# FX_I2C_Proto_Shield_v9.net
KiCad netlist of a schematic drawn in EAGLE
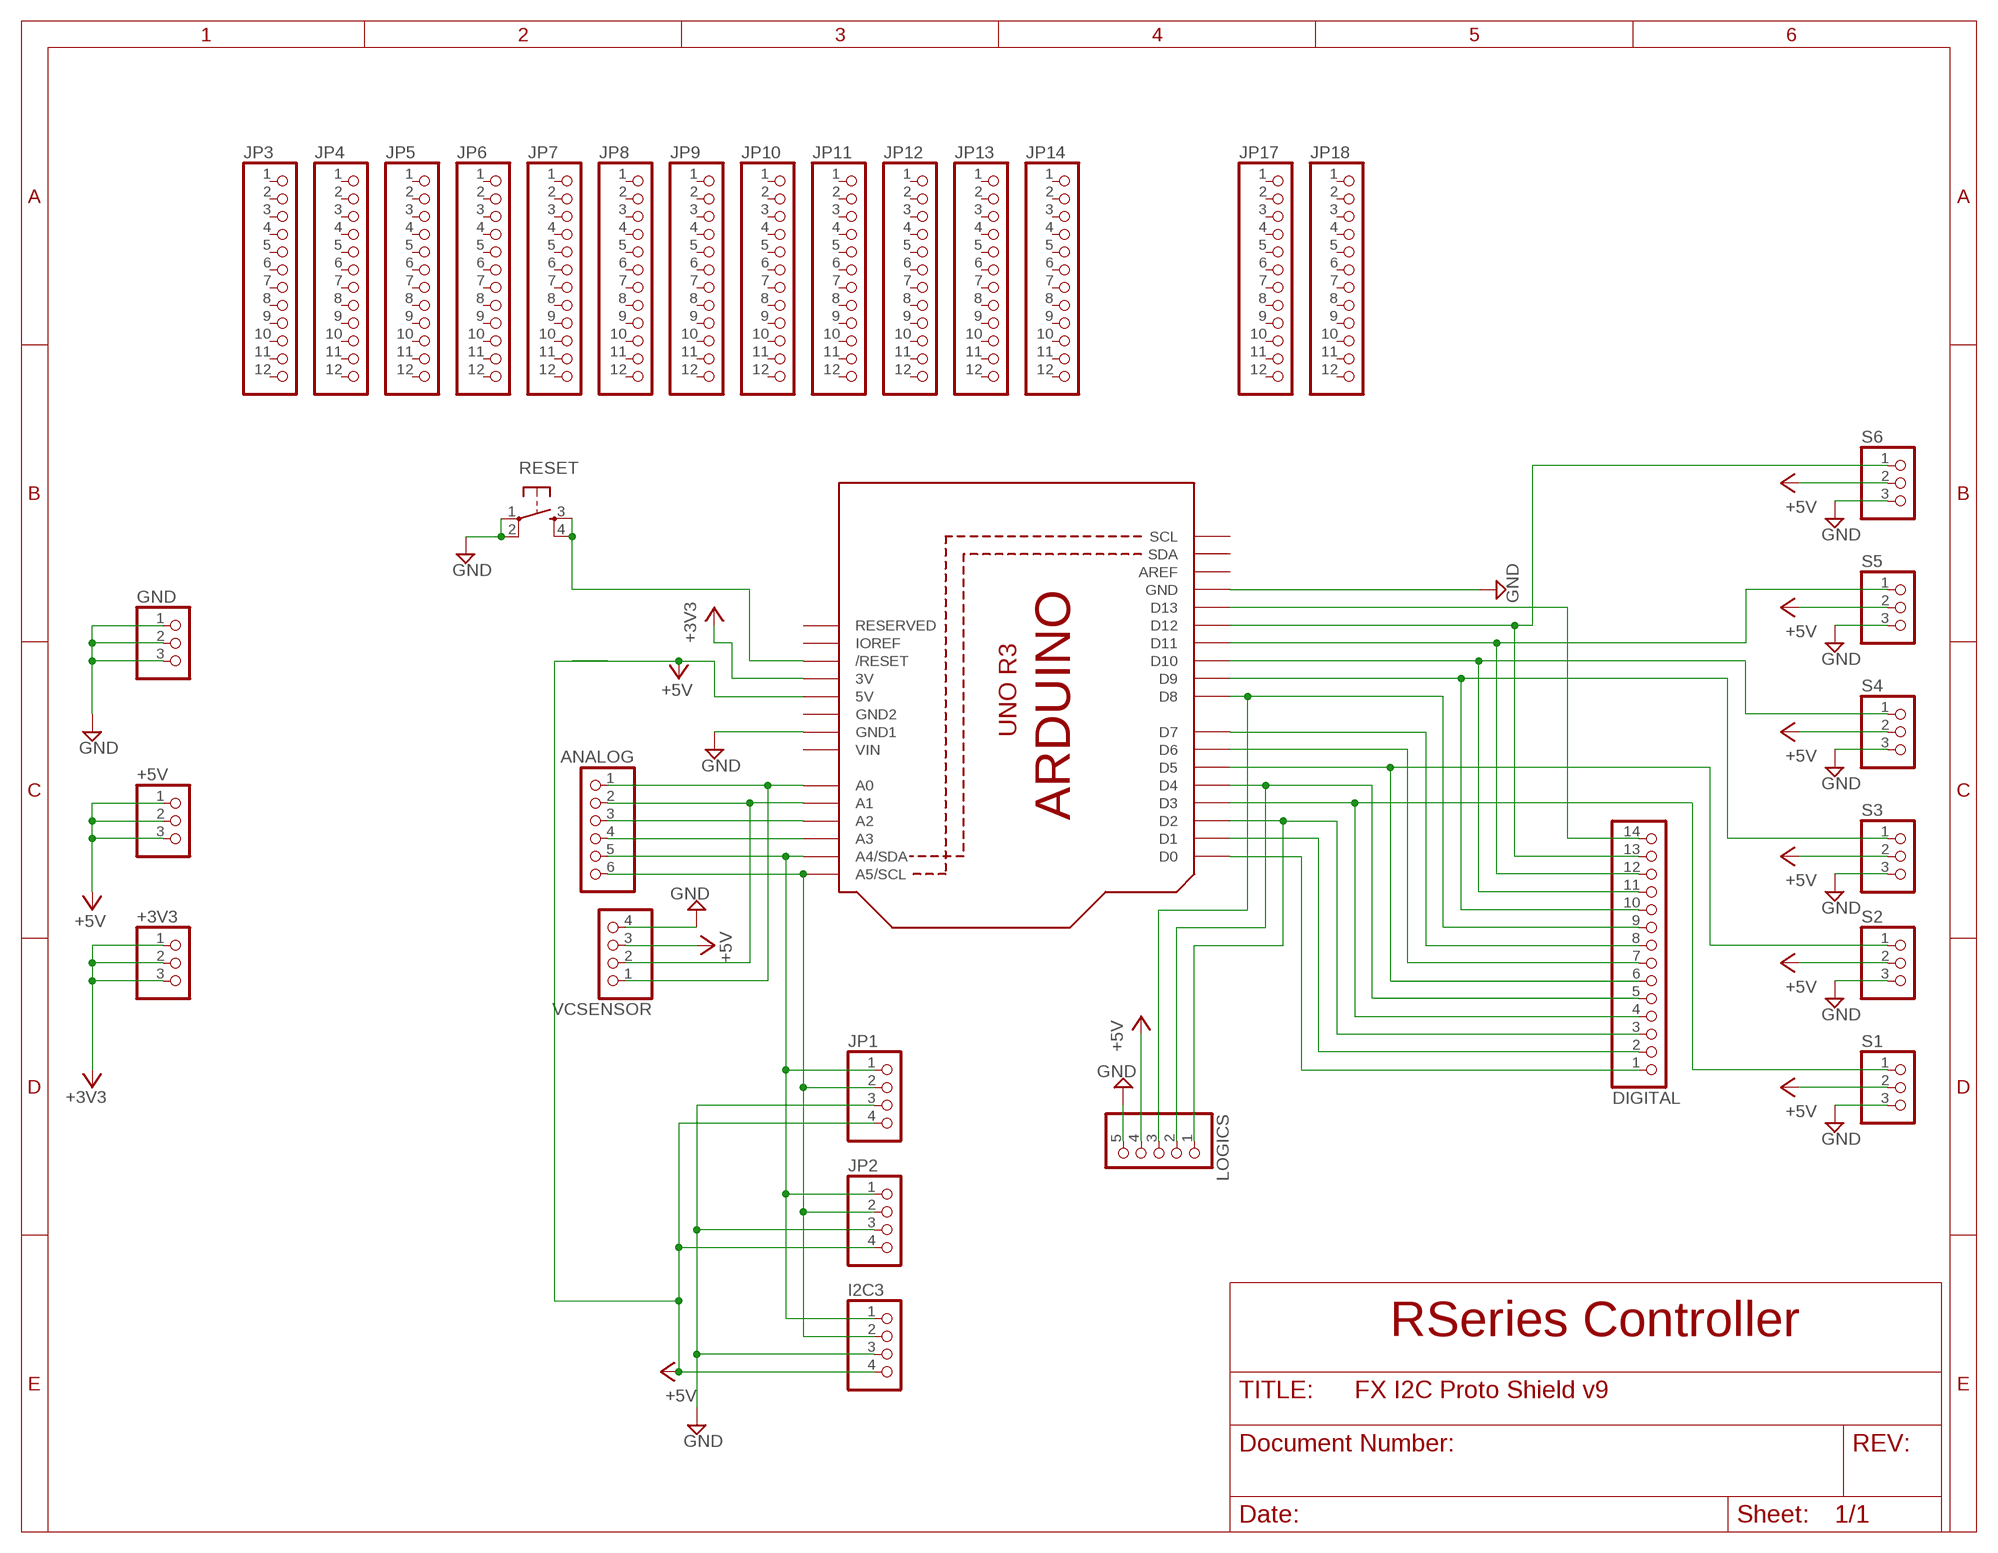
[diagram p0: schematic, sheet 1]

(export (version "E")
  (design (tool "Eeschema 10.0.6"))
  (components
    (comp (ref "+3V3")
      (value "PINHD-1X3CB")
      (footprint "eagle-import:1X03-CLEANBIG")
      (libsource (lib "eagle-import") (part "PINHD-1X3CB"))
    )
    (comp (ref "+5V")
      (value "PINHD-1X3CB")
      (footprint "eagle-import:1X03-CLEANBIG")
      (libsource (lib "eagle-import") (part "PINHD-1X3CB"))
    )
    (comp (ref "ANALOG")
      (value "PINHD-1X6B")
      (footprint "eagle-import:1X06-BIG")
      (libsource (lib "eagle-import") (part "PINHD-1X6B"))
    )
    (comp (ref "DIGITAL")
      (value "PINHD-1X14-CB")
      (footprint "eagle-import:1X14-CB")
      (libsource (lib "eagle-import") (part "PINHD-1X14-CB"))
    )
    (comp (ref "GND")
      (value "PINHD-1X3CB")
      (footprint "eagle-import:1X03-CLEANBIG")
      (libsource (lib "eagle-import") (part "PINHD-1X3CB"))
    )
    (comp (ref "I2C3")
      (value "PINHD-1X4")
      (footprint "eagle-import:1X04")
      (libsource (lib "eagle-import") (part "PINHD-1X4"))
    )
    (comp (ref "JP1")
      (value "PINHD-1X4")
      (footprint "eagle-import:1X04")
      (libsource (lib "eagle-import") (part "PINHD-1X4"))
    )
    (comp (ref "JP2")
      (value "PINHD-1X4")
      (footprint "eagle-import:1X04")
      (libsource (lib "eagle-import") (part "PINHD-1X4"))
    )
    (comp (ref "JP3")
      (value "PINHD-1X12-CB")
      (footprint "eagle-import:1X12-CB")
      (libsource (lib "eagle-import") (part "PINHD-1X12-CB"))
    )
    (comp (ref "JP4")
      (value "PINHD-1X12-CB")
      (footprint "eagle-import:1X12-CB")
      (libsource (lib "eagle-import") (part "PINHD-1X12-CB"))
    )
    (comp (ref "JP5")
      (value "PINHD-1X12-CB")
      (footprint "eagle-import:1X12-CB")
      (libsource (lib "eagle-import") (part "PINHD-1X12-CB"))
    )
    (comp (ref "JP6")
      (value "PINHD-1X12-CB")
      (footprint "eagle-import:1X12-CB")
      (libsource (lib "eagle-import") (part "PINHD-1X12-CB"))
    )
    (comp (ref "JP7")
      (value "PINHD-1X12-CB")
      (footprint "eagle-import:1X12-CB")
      (libsource (lib "eagle-import") (part "PINHD-1X12-CB"))
    )
    (comp (ref "JP8")
      (value "PINHD-1X12-CB")
      (footprint "eagle-import:1X12-CB")
      (libsource (lib "eagle-import") (part "PINHD-1X12-CB"))
    )
    (comp (ref "JP9")
      (value "PINHD-1X12-CB")
      (footprint "eagle-import:1X12-CB")
      (libsource (lib "eagle-import") (part "PINHD-1X12-CB"))
    )
    (comp (ref "JP10")
      (value "PINHD-1X12-CB")
      (footprint "eagle-import:1X12-CB")
      (libsource (lib "eagle-import") (part "PINHD-1X12-CB"))
    )
    (comp (ref "JP11")
      (value "PINHD-1X12-CB")
      (footprint "eagle-import:1X12-CB")
      (libsource (lib "eagle-import") (part "PINHD-1X12-CB"))
    )
    (comp (ref "JP12")
      (value "PINHD-1X12-CB")
      (footprint "eagle-import:1X12-CB")
      (libsource (lib "eagle-import") (part "PINHD-1X12-CB"))
    )
    (comp (ref "JP13")
      (value "PINHD-1X12-CB")
      (footprint "eagle-import:1X12-CB")
      (libsource (lib "eagle-import") (part "PINHD-1X12-CB"))
    )
    (comp (ref "JP14")
      (value "PINHD-1X12-CB")
      (footprint "eagle-import:1X12-CB")
      (libsource (lib "eagle-import") (part "PINHD-1X12-CB"))
    )
    (comp (ref "JP17")
      (value "PINHD-1X12-CB")
      (footprint "eagle-import:1X12-CB")
      (libsource (lib "eagle-import") (part "PINHD-1X12-CB"))
    )
    (comp (ref "JP18")
      (value "PINHD-1X12-CB")
      (footprint "eagle-import:1X12-CB")
      (libsource (lib "eagle-import") (part "PINHD-1X12-CB"))
    )
    (comp (ref "LOGICS")
      (value "PINHD-1X5")
      (footprint "eagle-import:1X05")
      (libsource (lib "eagle-import") (part "PINHD-1X5"))
    )
    (comp (ref "RESET")
      (value "TAC_SWITCHPTH")
      (footprint "eagle-import:TACTILE-PTH")
      (libsource (lib "eagle-import") (part "TAC_SWITCHPTH"))
    )
    (comp (ref "S1")
      (value "PINHD-1X3")
      (footprint "eagle-import:1X03")
      (libsource (lib "eagle-import") (part "PINHD-1X3"))
    )
    (comp (ref "S2")
      (value "PINHD-1X3")
      (footprint "eagle-import:1X03")
      (libsource (lib "eagle-import") (part "PINHD-1X3"))
    )
    (comp (ref "S3")
      (value "PINHD-1X3")
      (footprint "eagle-import:1X03")
      (libsource (lib "eagle-import") (part "PINHD-1X3"))
    )
    (comp (ref "S4")
      (value "PINHD-1X3")
      (footprint "eagle-import:1X03")
      (libsource (lib "eagle-import") (part "PINHD-1X3"))
    )
    (comp (ref "S5")
      (value "PINHD-1X3")
      (footprint "eagle-import:1X03")
      (libsource (lib "eagle-import") (part "PINHD-1X3"))
    )
    (comp (ref "S6")
      (value "PINHD-1X3")
      (footprint "eagle-import:1X03")
      (libsource (lib "eagle-import") (part "PINHD-1X3"))
    )
    (comp (ref "U1")
      (value "ARDUINOR3-DIMENSION")
      (footprint "eagle-import:ARDUINOR3")
      (libsource (lib "eagle-import") (part "ARDUINOR3-DIMENSION"))
    )
    (comp (ref "VCSENSOR")
      (value "PINHD-1X4")
      (footprint "eagle-import:1X04")
      (libsource (lib "eagle-import") (part "PINHD-1X4"))
    )
  )
  (nets
    (net (code "1") (name "+3V3") (class "Default")
      (node (ref "+3V3") (pin "1") (pinfunction "1_1") (pintype "passive"))
      (node (ref "+3V3") (pin "2") (pinfunction "2_2") (pintype "passive"))
      (node (ref "+3V3") (pin "3") (pinfunction "3_3") (pintype "passive"))
      (node (ref "U1") (pin "3V") (pinfunction "3V_3V") (pintype "power_in"))
    )
    (net (code "2") (name "+5V") (class "Default")
      (node (ref "+5V") (pin "1") (pinfunction "1_1") (pintype "passive"))
      (node (ref "+5V") (pin "2") (pinfunction "2_2") (pintype "passive"))
      (node (ref "+5V") (pin "3") (pinfunction "3_3") (pintype "passive"))
      (node (ref "I2C3") (pin "4") (pinfunction "4_4") (pintype "passive"))
      (node (ref "JP1") (pin "4") (pinfunction "4_4") (pintype "passive"))
      (node (ref "JP2") (pin "4") (pinfunction "4_4") (pintype "passive"))
      (node (ref "LOGICS") (pin "4") (pinfunction "4_4") (pintype "passive"))
      (node (ref "S1") (pin "2") (pinfunction "2_2") (pintype "passive"))
      (node (ref "S2") (pin "2") (pinfunction "2_2") (pintype "passive"))
      (node (ref "S3") (pin "2") (pinfunction "2_2") (pintype "passive"))
      (node (ref "S4") (pin "2") (pinfunction "2_2") (pintype "passive"))
      (node (ref "S5") (pin "2") (pinfunction "2_2") (pintype "passive"))
      (node (ref "S6") (pin "2") (pinfunction "2_2") (pintype "passive"))
      (node (ref "U1") (pin "5V") (pinfunction "5V_5V") (pintype "power_in"))
      (node (ref "VCSENSOR") (pin "3") (pinfunction "3_3") (pintype "passive"))
    )
    (net (code "3") (name "/GND2") (class "Default")
      (node (ref "U1") (pin "GND2") (pinfunction "GND2_GND2") (pintype "power_in"))
    )
    (net (code "4") (name "/VIN") (class "Default")
      (node (ref "U1") (pin "VIN") (pinfunction "VIN_VIN") (pintype "power_in"))
    )
    (net (code "5") (name "GND") (class "Default")
      (node (ref "GND") (pin "1") (pinfunction "1_1") (pintype "passive"))
      (node (ref "GND") (pin "2") (pinfunction "2_2") (pintype "passive"))
      (node (ref "GND") (pin "3") (pinfunction "3_3") (pintype "passive"))
      (node (ref "I2C3") (pin "3") (pinfunction "3_3") (pintype "passive"))
      (node (ref "JP1") (pin "3") (pinfunction "3_3") (pintype "passive"))
      (node (ref "JP2") (pin "3") (pinfunction "3_3") (pintype "passive"))
      (node (ref "LOGICS") (pin "5") (pinfunction "5_5") (pintype "passive"))
      (node (ref "RESET") (pin "1") (pinfunction "1_1") (pintype "passive"))
      (node (ref "RESET") (pin "2") (pinfunction "2_2") (pintype "passive"))
      (node (ref "S1") (pin "3") (pinfunction "3_3") (pintype "passive"))
      (node (ref "S2") (pin "3") (pinfunction "3_3") (pintype "passive"))
      (node (ref "S3") (pin "3") (pinfunction "3_3") (pintype "passive"))
      (node (ref "S4") (pin "3") (pinfunction "3_3") (pintype "passive"))
      (node (ref "S5") (pin "3") (pinfunction "3_3") (pintype "passive"))
      (node (ref "S6") (pin "3") (pinfunction "3_3") (pintype "passive"))
      (node (ref "U1") (pin "GND") (pinfunction "GND_GND") (pintype "power_in"))
      (node (ref "U1") (pin "GND1") (pinfunction "GND1_GND1") (pintype "power_in"))
      (node (ref "VCSENSOR") (pin "4") (pinfunction "4_4") (pintype "passive"))
    )
    (net (code "6") (name "Net-(ANALOG-Pad1)") (class "Default")
      (node (ref "ANALOG") (pin "1") (pinfunction "1_1") (pintype "passive"))
      (node (ref "U1") (pin "A0") (pinfunction "A0_A0") (pintype "bidirectional"))
      (node (ref "VCSENSOR") (pin "1") (pinfunction "1_1") (pintype "passive"))
    )
    (net (code "7") (name "Net-(ANALOG-Pad2)") (class "Default")
      (node (ref "ANALOG") (pin "2") (pinfunction "2_2") (pintype "passive"))
      (node (ref "U1") (pin "A1") (pinfunction "A1_A1") (pintype "bidirectional"))
      (node (ref "VCSENSOR") (pin "2") (pinfunction "2_2") (pintype "passive"))
    )
    (net (code "8") (name "Net-(ANALOG-Pad3)") (class "Default")
      (node (ref "ANALOG") (pin "3") (pinfunction "3_3") (pintype "passive"))
      (node (ref "U1") (pin "A2") (pinfunction "A2_A2") (pintype "bidirectional"))
    )
    (net (code "9") (name "Net-(ANALOG-Pad4)") (class "Default")
      (node (ref "ANALOG") (pin "4") (pinfunction "4_4") (pintype "passive"))
      (node (ref "U1") (pin "A3") (pinfunction "A3_A3") (pintype "bidirectional"))
    )
    (net (code "10") (name "Net-(DIGITAL-Pad1)") (class "Default")
      (node (ref "DIGITAL") (pin "1") (pinfunction "1_1") (pintype "passive"))
      (node (ref "U1") (pin "D0") (pinfunction "D0_D0") (pintype "bidirectional"))
    )
    (net (code "11") (name "Net-(DIGITAL-Pad2)") (class "Default")
      (node (ref "DIGITAL") (pin "2") (pinfunction "2_2") (pintype "passive"))
      (node (ref "U1") (pin "D1") (pinfunction "D1_D1") (pintype "bidirectional"))
    )
    (net (code "12") (name "Net-(DIGITAL-Pad3)") (class "Default")
      (node (ref "DIGITAL") (pin "3") (pinfunction "3_3") (pintype "passive"))
      (node (ref "LOGICS") (pin "1") (pinfunction "1_1") (pintype "passive"))
      (node (ref "U1") (pin "D2") (pinfunction "D2_D2") (pintype "bidirectional"))
    )
    (net (code "13") (name "Net-(DIGITAL-Pad4)") (class "Default")
      (node (ref "DIGITAL") (pin "4") (pinfunction "4_4") (pintype "passive"))
      (node (ref "S1") (pin "1") (pinfunction "1_1") (pintype "passive"))
      (node (ref "U1") (pin "D3") (pinfunction "D3_D3") (pintype "bidirectional"))
    )
    (net (code "14") (name "Net-(DIGITAL-Pad5)") (class "Default")
      (node (ref "DIGITAL") (pin "5") (pinfunction "5_5") (pintype "passive"))
      (node (ref "LOGICS") (pin "2") (pinfunction "2_2") (pintype "passive"))
      (node (ref "U1") (pin "D4") (pinfunction "D4_D4") (pintype "bidirectional"))
    )
    (net (code "15") (name "Net-(DIGITAL-Pad6)") (class "Default")
      (node (ref "DIGITAL") (pin "6") (pinfunction "6_6") (pintype "passive"))
      (node (ref "S2") (pin "1") (pinfunction "1_1") (pintype "passive"))
      (node (ref "U1") (pin "D5") (pinfunction "D5_D5") (pintype "bidirectional"))
    )
    (net (code "16") (name "Net-(DIGITAL-Pad7)") (class "Default")
      (node (ref "DIGITAL") (pin "7") (pinfunction "7_7") (pintype "passive"))
      (node (ref "U1") (pin "D6") (pinfunction "D6_D6") (pintype "bidirectional"))
    )
    (net (code "17") (name "Net-(DIGITAL-Pad8)") (class "Default")
      (node (ref "DIGITAL") (pin "8") (pinfunction "8_8") (pintype "passive"))
      (node (ref "U1") (pin "D7") (pinfunction "D7_D7") (pintype "bidirectional"))
    )
    (net (code "18") (name "Net-(DIGITAL-Pad9)") (class "Default")
      (node (ref "DIGITAL") (pin "9") (pinfunction "9_9") (pintype "passive"))
      (node (ref "LOGICS") (pin "3") (pinfunction "3_3") (pintype "passive"))
      (node (ref "U1") (pin "D8") (pinfunction "D8_D8") (pintype "bidirectional"))
    )
    (net (code "19") (name "Net-(DIGITAL-Pad10)") (class "Default")
      (node (ref "DIGITAL") (pin "10") (pinfunction "10_10") (pintype "passive"))
      (node (ref "S3") (pin "1") (pinfunction "1_1") (pintype "passive"))
      (node (ref "U1") (pin "D9") (pinfunction "D9_D9") (pintype "bidirectional"))
    )
    (net (code "20") (name "Net-(DIGITAL-Pad11)") (class "Default")
      (node (ref "DIGITAL") (pin "11") (pinfunction "11_11") (pintype "passive"))
      (node (ref "S4") (pin "1") (pinfunction "1_1") (pintype "passive"))
      (node (ref "U1") (pin "D10") (pinfunction "D10_D10") (pintype "bidirectional"))
    )
    (net (code "21") (name "Net-(DIGITAL-Pad12)") (class "Default")
      (node (ref "DIGITAL") (pin "12") (pinfunction "12_12") (pintype "passive"))
      (node (ref "S5") (pin "1") (pinfunction "1_1") (pintype "passive"))
      (node (ref "U1") (pin "D11") (pinfunction "D11_D11") (pintype "bidirectional"))
    )
    (net (code "22") (name "Net-(DIGITAL-Pad13)") (class "Default")
      (node (ref "DIGITAL") (pin "13") (pinfunction "13_13") (pintype "passive"))
      (node (ref "S6") (pin "1") (pinfunction "1_1") (pintype "passive"))
      (node (ref "U1") (pin "D12") (pinfunction "D12_D12") (pintype "bidirectional"))
    )
    (net (code "23") (name "Net-(DIGITAL-Pad14)") (class "Default")
      (node (ref "DIGITAL") (pin "14") (pinfunction "14_14") (pintype "passive"))
      (node (ref "U1") (pin "D13") (pinfunction "D13_D13") (pintype "bidirectional"))
    )
    (net (code "24") (name "Net-(U1-A4{slash}SDA)") (class "Default")
      (node (ref "ANALOG") (pin "5") (pinfunction "5_5") (pintype "passive"))
      (node (ref "I2C3") (pin "1") (pinfunction "1_1") (pintype "passive"))
      (node (ref "JP1") (pin "1") (pinfunction "1_1") (pintype "passive"))
      (node (ref "JP2") (pin "1") (pinfunction "1_1") (pintype "passive"))
      (node (ref "U1") (pin "A4") (pinfunction "A4/SDA_A4") (pintype "bidirectional"))
    )
    (net (code "25") (name "Net-(U1-A5{slash}SCL)") (class "Default")
      (node (ref "ANALOG") (pin "6") (pinfunction "6_6") (pintype "passive"))
      (node (ref "I2C3") (pin "2") (pinfunction "2_2") (pintype "passive"))
      (node (ref "JP1") (pin "2") (pinfunction "2_2") (pintype "passive"))
      (node (ref "JP2") (pin "2") (pinfunction "2_2") (pintype "passive"))
      (node (ref "U1") (pin "A5") (pinfunction "A5/SCL_A5") (pintype "bidirectional"))
    )
    (net (code "26") (name "Net-(U1-{slash}RESET)") (class "Default")
      (node (ref "RESET") (pin "3") (pinfunction "3_3") (pintype "passive"))
      (node (ref "RESET") (pin "4") (pinfunction "4_4") (pintype "passive"))
      (node (ref "U1") (pin "RESET") (pinfunction "/RESET_RESET") (pintype "bidirectional"))
    )
    (net (code "27") (name "unconnected-(JP3-Pad1)") (class "Default")
      (node (ref "JP3") (pin "1") (pinfunction "1_1") (pintype "passive"))
    )
    (net (code "28") (name "unconnected-(JP3-Pad2)") (class "Default")
      (node (ref "JP3") (pin "2") (pinfunction "2_2") (pintype "passive"))
    )
    (net (code "29") (name "unconnected-(JP3-Pad3)") (class "Default")
      (node (ref "JP3") (pin "3") (pinfunction "3_3") (pintype "passive"))
    )
    (net (code "30") (name "unconnected-(JP3-Pad4)") (class "Default")
      (node (ref "JP3") (pin "4") (pinfunction "4_4") (pintype "passive"))
    )
    (net (code "31") (name "unconnected-(JP3-Pad5)") (class "Default")
      (node (ref "JP3") (pin "5") (pinfunction "5_5") (pintype "passive"))
    )
    (net (code "32") (name "unconnected-(JP3-Pad6)") (class "Default")
      (node (ref "JP3") (pin "6") (pinfunction "6_6") (pintype "passive"))
    )
    (net (code "33") (name "unconnected-(JP3-Pad7)") (class "Default")
      (node (ref "JP3") (pin "7") (pinfunction "7_7") (pintype "passive"))
    )
    (net (code "34") (name "unconnected-(JP3-Pad8)") (class "Default")
      (node (ref "JP3") (pin "8") (pinfunction "8_8") (pintype "passive"))
    )
    (net (code "35") (name "unconnected-(JP3-Pad9)") (class "Default")
      (node (ref "JP3") (pin "9") (pinfunction "9_9") (pintype "passive"))
    )
    (net (code "36") (name "unconnected-(JP3-Pad10)") (class "Default")
      (node (ref "JP3") (pin "10") (pinfunction "10_10") (pintype "passive"))
    )
    (net (code "37") (name "unconnected-(JP3-Pad11)") (class "Default")
      (node (ref "JP3") (pin "11") (pinfunction "11_11") (pintype "passive"))
    )
    (net (code "38") (name "unconnected-(JP3-Pad12)") (class "Default")
      (node (ref "JP3") (pin "12") (pinfunction "12_12") (pintype "passive"))
    )
    (net (code "39") (name "unconnected-(JP4-Pad1)") (class "Default")
      (node (ref "JP4") (pin "1") (pinfunction "1_1") (pintype "passive"))
    )
    (net (code "40") (name "unconnected-(JP4-Pad2)") (class "Default")
      (node (ref "JP4") (pin "2") (pinfunction "2_2") (pintype "passive"))
    )
    (net (code "41") (name "unconnected-(JP4-Pad3)") (class "Default")
      (node (ref "JP4") (pin "3") (pinfunction "3_3") (pintype "passive"))
    )
    (net (code "42") (name "unconnected-(JP4-Pad4)") (class "Default")
      (node (ref "JP4") (pin "4") (pinfunction "4_4") (pintype "passive"))
    )
    (net (code "43") (name "unconnected-(JP4-Pad5)") (class "Default")
      (node (ref "JP4") (pin "5") (pinfunction "5_5") (pintype "passive"))
    )
    (net (code "44") (name "unconnected-(JP4-Pad6)") (class "Default")
      (node (ref "JP4") (pin "6") (pinfunction "6_6") (pintype "passive"))
    )
    (net (code "45") (name "unconnected-(JP4-Pad7)") (class "Default")
      (node (ref "JP4") (pin "7") (pinfunction "7_7") (pintype "passive"))
    )
    (net (code "46") (name "unconnected-(JP4-Pad8)") (class "Default")
      (node (ref "JP4") (pin "8") (pinfunction "8_8") (pintype "passive"))
    )
    (net (code "47") (name "unconnected-(JP4-Pad9)") (class "Default")
      (node (ref "JP4") (pin "9") (pinfunction "9_9") (pintype "passive"))
    )
    (net (code "48") (name "unconnected-(JP4-Pad10)") (class "Default")
      (node (ref "JP4") (pin "10") (pinfunction "10_10") (pintype "passive"))
    )
    (net (code "49") (name "unconnected-(JP4-Pad11)") (class "Default")
      (node (ref "JP4") (pin "11") (pinfunction "11_11") (pintype "passive"))
    )
    (net (code "50") (name "unconnected-(JP4-Pad12)") (class "Default")
      (node (ref "JP4") (pin "12") (pinfunction "12_12") (pintype "passive"))
    )
    (net (code "51") (name "unconnected-(JP5-Pad1)") (class "Default")
      (node (ref "JP5") (pin "1") (pinfunction "1_1") (pintype "passive"))
    )
    (net (code "52") (name "unconnected-(JP5-Pad2)") (class "Default")
      (node (ref "JP5") (pin "2") (pinfunction "2_2") (pintype "passive"))
    )
    (net (code "53") (name "unconnected-(JP5-Pad3)") (class "Default")
      (node (ref "JP5") (pin "3") (pinfunction "3_3") (pintype "passive"))
    )
    (net (code "54") (name "unconnected-(JP5-Pad4)") (class "Default")
      (node (ref "JP5") (pin "4") (pinfunction "4_4") (pintype "passive"))
    )
    (net (code "55") (name "unconnected-(JP5-Pad5)") (class "Default")
      (node (ref "JP5") (pin "5") (pinfunction "5_5") (pintype "passive"))
    )
    (net (code "56") (name "unconnected-(JP5-Pad6)") (class "Default")
      (node (ref "JP5") (pin "6") (pinfunction "6_6") (pintype "passive"))
    )
    (net (code "57") (name "unconnected-(JP5-Pad7)") (class "Default")
      (node (ref "JP5") (pin "7") (pinfunction "7_7") (pintype "passive"))
    )
    (net (code "58") (name "unconnected-(JP5-Pad8)") (class "Default")
      (node (ref "JP5") (pin "8") (pinfunction "8_8") (pintype "passive"))
    )
    (net (code "59") (name "unconnected-(JP5-Pad9)") (class "Default")
      (node (ref "JP5") (pin "9") (pinfunction "9_9") (pintype "passive"))
    )
    (net (code "60") (name "unconnected-(JP5-Pad10)") (class "Default")
      (node (ref "JP5") (pin "10") (pinfunction "10_10") (pintype "passive"))
    )
    (net (code "61") (name "unconnected-(JP5-Pad11)") (class "Default")
      (node (ref "JP5") (pin "11") (pinfunction "11_11") (pintype "passive"))
    )
    (net (code "62") (name "unconnected-(JP5-Pad12)") (class "Default")
      (node (ref "JP5") (pin "12") (pinfunction "12_12") (pintype "passive"))
    )
    (net (code "63") (name "unconnected-(JP6-Pad1)") (class "Default")
      (node (ref "JP6") (pin "1") (pinfunction "1_1") (pintype "passive"))
    )
    (net (code "64") (name "unconnected-(JP6-Pad2)") (class "Default")
      (node (ref "JP6") (pin "2") (pinfunction "2_2") (pintype "passive"))
    )
    (net (code "65") (name "unconnected-(JP6-Pad3)") (class "Default")
      (node (ref "JP6") (pin "3") (pinfunction "3_3") (pintype "passive"))
    )
    (net (code "66") (name "unconnected-(JP6-Pad4)") (class "Default")
      (node (ref "JP6") (pin "4") (pinfunction "4_4") (pintype "passive"))
    )
    (net (code "67") (name "unconnected-(JP6-Pad5)") (class "Default")
      (node (ref "JP6") (pin "5") (pinfunction "5_5") (pintype "passive"))
    )
    (net (code "68") (name "unconnected-(JP6-Pad6)") (class "Default")
      (node (ref "JP6") (pin "6") (pinfunction "6_6") (pintype "passive"))
    )
    (net (code "69") (name "unconnected-(JP6-Pad7)") (class "Default")
      (node (ref "JP6") (pin "7") (pinfunction "7_7") (pintype "passive"))
    )
    (net (code "70") (name "unconnected-(JP6-Pad8)") (class "Default")
      (node (ref "JP6") (pin "8") (pinfunction "8_8") (pintype "passive"))
    )
    (net (code "71") (name "unconnected-(JP6-Pad9)") (class "Default")
      (node (ref "JP6") (pin "9") (pinfunction "9_9") (pintype "passive"))
    )
    (net (code "72") (name "unconnected-(JP6-Pad10)") (class "Default")
      (node (ref "JP6") (pin "10") (pinfunction "10_10") (pintype "passive"))
    )
    (net (code "73") (name "unconnected-(JP6-Pad11)") (class "Default")
      (node (ref "JP6") (pin "11") (pinfunction "11_11") (pintype "passive"))
    )
    (net (code "74") (name "unconnected-(JP6-Pad12)") (class "Default")
      (node (ref "JP6") (pin "12") (pinfunction "12_12") (pintype "passive"))
    )
    (net (code "75") (name "unconnected-(JP7-Pad1)") (class "Default")
      (node (ref "JP7") (pin "1") (pinfunction "1_1") (pintype "passive"))
    )
    (net (code "76") (name "unconnected-(JP7-Pad2)") (class "Default")
      (node (ref "JP7") (pin "2") (pinfunction "2_2") (pintype "passive"))
    )
    (net (code "77") (name "unconnected-(JP7-Pad3)") (class "Default")
      (node (ref "JP7") (pin "3") (pinfunction "3_3") (pintype "passive"))
    )
    (net (code "78") (name "unconnected-(JP7-Pad4)") (class "Default")
      (node (ref "JP7") (pin "4") (pinfunction "4_4") (pintype "passive"))
    )
    (net (code "79") (name "unconnected-(JP7-Pad5)") (class "Default")
      (node (ref "JP7") (pin "5") (pinfunction "5_5") (pintype "passive"))
    )
    (net (code "80") (name "unconnected-(JP7-Pad6)") (class "Default")
      (node (ref "JP7") (pin "6") (pinfunction "6_6") (pintype "passive"))
    )
    (net (code "81") (name "unconnected-(JP7-Pad7)") (class "Default")
      (node (ref "JP7") (pin "7") (pinfunction "7_7") (pintype "passive"))
    )
    (net (code "82") (name "unconnected-(JP7-Pad8)") (class "Default")
      (node (ref "JP7") (pin "8") (pinfunction "8_8") (pintype "passive"))
    )
    (net (code "83") (name "unconnected-(JP7-Pad9)") (class "Default")
      (node (ref "JP7") (pin "9") (pinfunction "9_9") (pintype "passive"))
    )
    (net (code "84") (name "unconnected-(JP7-Pad10)") (class "Default")
      (node (ref "JP7") (pin "10") (pinfunction "10_10") (pintype "passive"))
    )
    (net (code "85") (name "unconnected-(JP7-Pad11)") (class "Default")
      (node (ref "JP7") (pin "11") (pinfunction "11_11") (pintype "passive"))
    )
    (net (code "86") (name "unconnected-(JP7-Pad12)") (class "Default")
      (node (ref "JP7") (pin "12") (pinfunction "12_12") (pintype "passive"))
    )
    (net (code "87") (name "unconnected-(JP8-Pad1)") (class "Default")
      (node (ref "JP8") (pin "1") (pinfunction "1_1") (pintype "passive"))
    )
    (net (code "88") (name "unconnected-(JP8-Pad2)") (class "Default")
      (node (ref "JP8") (pin "2") (pinfunction "2_2") (pintype "passive"))
    )
    (net (code "89") (name "unconnected-(JP8-Pad3)") (class "Default")
      (node (ref "JP8") (pin "3") (pinfunction "3_3") (pintype "passive"))
    )
    (net (code "90") (name "unconnected-(JP8-Pad4)") (class "Default")
      (node (ref "JP8") (pin "4") (pinfunction "4_4") (pintype "passive"))
    )
    (net (code "91") (name "unconnected-(JP8-Pad5)") (class "Default")
      (node (ref "JP8") (pin "5") (pinfunction "5_5") (pintype "passive"))
    )
    (net (code "92") (name "unconnected-(JP8-Pad6)") (class "Default")
      (node (ref "JP8") (pin "6") (pinfunction "6_6") (pintype "passive"))
    )
    (net (code "93") (name "unconnected-(JP8-Pad7)") (class "Default")
      (node (ref "JP8") (pin "7") (pinfunction "7_7") (pintype "passive"))
    )
    (net (code "94") (name "unconnected-(JP8-Pad8)") (class "Default")
      (node (ref "JP8") (pin "8") (pinfunction "8_8") (pintype "passive"))
    )
    (net (code "95") (name "unconnected-(JP8-Pad9)") (class "Default")
      (node (ref "JP8") (pin "9") (pinfunction "9_9") (pintype "passive"))
    )
    (net (code "96") (name "unconnected-(JP8-Pad10)") (class "Default")
      (node (ref "JP8") (pin "10") (pinfunction "10_10") (pintype "passive"))
    )
    (net (code "97") (name "unconnected-(JP8-Pad11)") (class "Default")
      (node (ref "JP8") (pin "11") (pinfunction "11_11") (pintype "passive"))
    )
    (net (code "98") (name "unconnected-(JP8-Pad12)") (class "Default")
      (node (ref "JP8") (pin "12") (pinfunction "12_12") (pintype "passive"))
    )
    (net (code "99") (name "unconnected-(JP9-Pad1)") (class "Default")
      (node (ref "JP9") (pin "1") (pinfunction "1_1") (pintype "passive"))
    )
    (net (code "100") (name "unconnected-(JP9-Pad2)") (class "Default")
      (node (ref "JP9") (pin "2") (pinfunction "2_2") (pintype "passive"))
    )
    (net (code "101") (name "unconnected-(JP9-Pad3)") (class "Default")
      (node (ref "JP9") (pin "3") (pinfunction "3_3") (pintype "passive"))
    )
    (net (code "102") (name "unconnected-(JP9-Pad4)") (class "Default")
      (node (ref "JP9") (pin "4") (pinfunction "4_4") (pintype "passive"))
    )
    (net (code "103") (name "unconnected-(JP9-Pad5)") (class "Default")
      (node (ref "JP9") (pin "5") (pinfunction "5_5") (pintype "passive"))
    )
    (net (code "104") (name "unconnected-(JP9-Pad6)") (class "Default")
      (node (ref "JP9") (pin "6") (pinfunction "6_6") (pintype "passive"))
    )
    (net (code "105") (name "unconnected-(JP9-Pad7)") (class "Default")
      (node (ref "JP9") (pin "7") (pinfunction "7_7") (pintype "passive"))
    )
    (net (code "106") (name "unconnected-(JP9-Pad8)") (class "Default")
      (node (ref "JP9") (pin "8") (pinfunction "8_8") (pintype "passive"))
    )
    (net (code "107") (name "unconnected-(JP9-Pad9)") (class "Default")
      (node (ref "JP9") (pin "9") (pinfunction "9_9") (pintype "passive"))
    )
    (net (code "108") (name "unconnected-(JP9-Pad10)") (class "Default")
      (node (ref "JP9") (pin "10") (pinfunction "10_10") (pintype "passive"))
    )
    (net (code "109") (name "unconnected-(JP9-Pad11)") (class "Default")
      (node (ref "JP9") (pin "11") (pinfunction "11_11") (pintype "passive"))
    )
    (net (code "110") (name "unconnected-(JP9-Pad12)") (class "Default")
      (node (ref "JP9") (pin "12") (pinfunction "12_12") (pintype "passive"))
    )
    (net (code "111") (name "unconnected-(JP10-Pad1)") (class "Default")
      (node (ref "JP10") (pin "1") (pinfunction "1_1") (pintype "passive"))
    )
    (net (code "112") (name "unconnected-(JP10-Pad2)") (class "Default")
      (node (ref "JP10") (pin "2") (pinfunction "2_2") (pintype "passive"))
    )
    (net (code "113") (name "unconnected-(JP10-Pad3)") (class "Default")
      (node (ref "JP10") (pin "3") (pinfunction "3_3") (pintype "passive"))
    )
    (net (code "114") (name "unconnected-(JP10-Pad4)") (class "Default")
      (node (ref "JP10") (pin "4") (pinfunction "4_4") (pintype "passive"))
    )
    (net (code "115") (name "unconnected-(JP10-Pad5)") (class "Default")
      (node (ref "JP10") (pin "5") (pinfunction "5_5") (pintype "passive"))
    )
    (net (code "116") (name "unconnected-(JP10-Pad6)") (class "Default")
      (node (ref "JP10") (pin "6") (pinfunction "6_6") (pintype "passive"))
    )
    (net (code "117") (name "unconnected-(JP10-Pad7)") (class "Default")
      (node (ref "JP10") (pin "7") (pinfunction "7_7") (pintype "passive"))
    )
    (net (code "118") (name "unconnected-(JP10-Pad8)") (class "Default")
      (node (ref "JP10") (pin "8") (pinfunction "8_8") (pintype "passive"))
    )
    (net (code "119") (name "unconnected-(JP10-Pad9)") (class "Default")
      (node (ref "JP10") (pin "9") (pinfunction "9_9") (pintype "passive"))
    )
    (net (code "120") (name "unconnected-(JP10-Pad10)") (class "Default")
      (node (ref "JP10") (pin "10") (pinfunction "10_10") (pintype "passive"))
    )
    (net (code "121") (name "unconnected-(JP10-Pad11)") (class "Default")
      (node (ref "JP10") (pin "11") (pinfunction "11_11") (pintype "passive"))
    )
    (net (code "122") (name "unconnected-(JP10-Pad12)") (class "Default")
      (node (ref "JP10") (pin "12") (pinfunction "12_12") (pintype "passive"))
    )
    (net (code "123") (name "unconnected-(JP11-Pad1)") (class "Default")
      (node (ref "JP11") (pin "1") (pinfunction "1_1") (pintype "passive"))
    )
    (net (code "124") (name "unconnected-(JP11-Pad2)") (class "Default")
      (node (ref "JP11") (pin "2") (pinfunction "2_2") (pintype "passive"))
    )
    (net (code "125") (name "unconnected-(JP11-Pad3)") (class "Default")
      (node (ref "JP11") (pin "3") (pinfunction "3_3") (pintype "passive"))
    )
    (net (code "126") (name "unconnected-(JP11-Pad4)") (class "Default")
      (node (ref "JP11") (pin "4") (pinfunction "4_4") (pintype "passive"))
    )
    (net (code "127") (name "unconnected-(JP11-Pad5)") (class "Default")
      (node (ref "JP11") (pin "5") (pinfunction "5_5") (pintype "passive"))
    )
    (net (code "128") (name "unconnected-(JP11-Pad6)") (class "Default")
      (node (ref "JP11") (pin "6") (pinfunction "6_6") (pintype "passive"))
    )
    (net (code "129") (name "unconnected-(JP11-Pad7)") (class "Default")
      (node (ref "JP11") (pin "7") (pinfunction "7_7") (pintype "passive"))
    )
    (net (code "130") (name "unconnected-(JP11-Pad8)") (class "Default")
      (node (ref "JP11") (pin "8") (pinfunction "8_8") (pintype "passive"))
    )
    (net (code "131") (name "unconnected-(JP11-Pad9)") (class "Default")
      (node (ref "JP11") (pin "9") (pinfunction "9_9") (pintype "passive"))
    )
    (net (code "132") (name "unconnected-(JP11-Pad10)") (class "Default")
      (node (ref "JP11") (pin "10") (pinfunction "10_10") (pintype "passive"))
    )
    (net (code "133") (name "unconnected-(JP11-Pad11)") (class "Default")
      (node (ref "JP11") (pin "11") (pinfunction "11_11") (pintype "passive"))
    )
    (net (code "134") (name "unconnected-(JP11-Pad12)") (class "Default")
      (node (ref "JP11") (pin "12") (pinfunction "12_12") (pintype "passive"))
    )
    (net (code "135") (name "unconnected-(JP12-Pad1)") (class "Default")
      (node (ref "JP12") (pin "1") (pinfunction "1_1") (pintype "passive"))
    )
    (net (code "136") (name "unconnected-(JP12-Pad2)") (class "Default")
      (node (ref "JP12") (pin "2") (pinfunction "2_2") (pintype "passive"))
    )
    (net (code "137") (name "unconnected-(JP12-Pad3)") (class "Default")
      (node (ref "JP12") (pin "3") (pinfunction "3_3") (pintype "passive"))
    )
    (net (code "138") (name "unconnected-(JP12-Pad4)") (class "Default")
      (node (ref "JP12") (pin "4") (pinfunction "4_4") (pintype "passive"))
    )
    (net (code "139") (name "unconnected-(JP12-Pad5)") (class "Default")
      (node (ref "JP12") (pin "5") (pinfunction "5_5") (pintype "passive"))
    )
    (net (code "140") (name "unconnected-(JP12-Pad6)") (class "Default")
      (node (ref "JP12") (pin "6") (pinfunction "6_6") (pintype "passive"))
    )
    (net (code "141") (name "unconnected-(JP12-Pad7)") (class "Default")
      (node (ref "JP12") (pin "7") (pinfunction "7_7") (pintype "passive"))
    )
    (net (code "142") (name "unconnected-(JP12-Pad8)") (class "Default")
      (node (ref "JP12") (pin "8") (pinfunction "8_8") (pintype "passive"))
    )
    (net (code "143") (name "unconnected-(JP12-Pad9)") (class "Default")
      (node (ref "JP12") (pin "9") (pinfunction "9_9") (pintype "passive"))
    )
    (net (code "144") (name "unconnected-(JP12-Pad10)") (class "Default")
      (node (ref "JP12") (pin "10") (pinfunction "10_10") (pintype "passive"))
    )
    (net (code "145") (name "unconnected-(JP12-Pad11)") (class "Default")
      (node (ref "JP12") (pin "11") (pinfunction "11_11") (pintype "passive"))
    )
    (net (code "146") (name "unconnected-(JP12-Pad12)") (class "Default")
      (node (ref "JP12") (pin "12") (pinfunction "12_12") (pintype "passive"))
    )
    (net (code "147") (name "unconnected-(JP13-Pad1)") (class "Default")
      (node (ref "JP13") (pin "1") (pinfunction "1_1") (pintype "passive"))
    )
    (net (code "148") (name "unconnected-(JP13-Pad2)") (class "Default")
      (node (ref "JP13") (pin "2") (pinfunction "2_2") (pintype "passive"))
    )
    (net (code "149") (name "unconnected-(JP13-Pad3)") (class "Default")
      (node (ref "JP13") (pin "3") (pinfunction "3_3") (pintype "passive"))
    )
    (net (code "150") (name "unconnected-(JP13-Pad4)") (class "Default")
      (node (ref "JP13") (pin "4") (pinfunction "4_4") (pintype "passive"))
    )
    (net (code "151") (name "unconnected-(JP13-Pad5)") (class "Default")
      (node (ref "JP13") (pin "5") (pinfunction "5_5") (pintype "passive"))
    )
    (net (code "152") (name "unconnected-(JP13-Pad6)") (class "Default")
      (node (ref "JP13") (pin "6") (pinfunction "6_6") (pintype "passive"))
    )
    (net (code "153") (name "unconnected-(JP13-Pad7)") (class "Default")
      (node (ref "JP13") (pin "7") (pinfunction "7_7") (pintype "passive"))
    )
    (net (code "154") (name "unconnected-(JP13-Pad8)") (class "Default")
      (node (ref "JP13") (pin "8") (pinfunction "8_8") (pintype "passive"))
    )
    (net (code "155") (name "unconnected-(JP13-Pad9)") (class "Default")
      (node (ref "JP13") (pin "9") (pinfunction "9_9") (pintype "passive"))
    )
    (net (code "156") (name "unconnected-(JP13-Pad10)") (class "Default")
      (node (ref "JP13") (pin "10") (pinfunction "10_10") (pintype "passive"))
    )
    (net (code "157") (name "unconnected-(JP13-Pad11)") (class "Default")
      (node (ref "JP13") (pin "11") (pinfunction "11_11") (pintype "passive"))
    )
    (net (code "158") (name "unconnected-(JP13-Pad12)") (class "Default")
      (node (ref "JP13") (pin "12") (pinfunction "12_12") (pintype "passive"))
    )
    (net (code "159") (name "unconnected-(JP14-Pad1)") (class "Default")
      (node (ref "JP14") (pin "1") (pinfunction "1_1") (pintype "passive"))
    )
    (net (code "160") (name "unconnected-(JP14-Pad2)") (class "Default")
      (node (ref "JP14") (pin "2") (pinfunction "2_2") (pintype "passive"))
    )
    (net (code "161") (name "unconnected-(JP14-Pad3)") (class "Default")
      (node (ref "JP14") (pin "3") (pinfunction "3_3") (pintype "passive"))
    )
    (net (code "162") (name "unconnected-(JP14-Pad4)") (class "Default")
      (node (ref "JP14") (pin "4") (pinfunction "4_4") (pintype "passive"))
    )
    (net (code "163") (name "unconnected-(JP14-Pad5)") (class "Default")
      (node (ref "JP14") (pin "5") (pinfunction "5_5") (pintype "passive"))
    )
    (net (code "164") (name "unconnected-(JP14-Pad6)") (class "Default")
      (node (ref "JP14") (pin "6") (pinfunction "6_6") (pintype "passive"))
    )
    (net (code "165") (name "unconnected-(JP14-Pad7)") (class "Default")
      (node (ref "JP14") (pin "7") (pinfunction "7_7") (pintype "passive"))
    )
    (net (code "166") (name "unconnected-(JP14-Pad8)") (class "Default")
      (node (ref "JP14") (pin "8") (pinfunction "8_8") (pintype "passive"))
    )
    (net (code "167") (name "unconnected-(JP14-Pad9)") (class "Default")
      (node (ref "JP14") (pin "9") (pinfunction "9_9") (pintype "passive"))
    )
    (net (code "168") (name "unconnected-(JP14-Pad10)") (class "Default")
      (node (ref "JP14") (pin "10") (pinfunction "10_10") (pintype "passive"))
    )
    (net (code "169") (name "unconnected-(JP14-Pad11)") (class "Default")
      (node (ref "JP14") (pin "11") (pinfunction "11_11") (pintype "passive"))
    )
    (net (code "170") (name "unconnected-(JP14-Pad12)") (class "Default")
      (node (ref "JP14") (pin "12") (pinfunction "12_12") (pintype "passive"))
    )
    (net (code "171") (name "unconnected-(JP17-Pad1)") (class "Default")
      (node (ref "JP17") (pin "1") (pinfunction "1_1") (pintype "passive"))
    )
    (net (code "172") (name "unconnected-(JP17-Pad2)") (class "Default")
      (node (ref "JP17") (pin "2") (pinfunction "2_2") (pintype "passive"))
    )
    (net (code "173") (name "unconnected-(JP17-Pad3)") (class "Default")
      (node (ref "JP17") (pin "3") (pinfunction "3_3") (pintype "passive"))
    )
    (net (code "174") (name "unconnected-(JP17-Pad4)") (class "Default")
      (node (ref "JP17") (pin "4") (pinfunction "4_4") (pintype "passive"))
    )
    (net (code "175") (name "unconnected-(JP17-Pad5)") (class "Default")
      (node (ref "JP17") (pin "5") (pinfunction "5_5") (pintype "passive"))
    )
    (net (code "176") (name "unconnected-(JP17-Pad6)") (class "Default")
      (node (ref "JP17") (pin "6") (pinfunction "6_6") (pintype "passive"))
    )
    (net (code "177") (name "unconnected-(JP17-Pad7)") (class "Default")
      (node (ref "JP17") (pin "7") (pinfunction "7_7") (pintype "passive"))
    )
    (net (code "178") (name "unconnected-(JP17-Pad8)") (class "Default")
      (node (ref "JP17") (pin "8") (pinfunction "8_8") (pintype "passive"))
    )
    (net (code "179") (name "unconnected-(JP17-Pad9)") (class "Default")
      (node (ref "JP17") (pin "9") (pinfunction "9_9") (pintype "passive"))
    )
    (net (code "180") (name "unconnected-(JP17-Pad10)") (class "Default")
      (node (ref "JP17") (pin "10") (pinfunction "10_10") (pintype "passive"))
    )
    (net (code "181") (name "unconnected-(JP17-Pad11)") (class "Default")
      (node (ref "JP17") (pin "11") (pinfunction "11_11") (pintype "passive"))
    )
    (net (code "182") (name "unconnected-(JP17-Pad12)") (class "Default")
      (node (ref "JP17") (pin "12") (pinfunction "12_12") (pintype "passive"))
    )
    (net (code "183") (name "unconnected-(JP18-Pad1)") (class "Default")
      (node (ref "JP18") (pin "1") (pinfunction "1_1") (pintype "passive"))
    )
    (net (code "184") (name "unconnected-(JP18-Pad2)") (class "Default")
      (node (ref "JP18") (pin "2") (pinfunction "2_2") (pintype "passive"))
    )
    (net (code "185") (name "unconnected-(JP18-Pad3)") (class "Default")
      (node (ref "JP18") (pin "3") (pinfunction "3_3") (pintype "passive"))
    )
    (net (code "186") (name "unconnected-(JP18-Pad4)") (class "Default")
      (node (ref "JP18") (pin "4") (pinfunction "4_4") (pintype "passive"))
    )
    (net (code "187") (name "unconnected-(JP18-Pad5)") (class "Default")
      (node (ref "JP18") (pin "5") (pinfunction "5_5") (pintype "passive"))
    )
    (net (code "188") (name "unconnected-(JP18-Pad6)") (class "Default")
      (node (ref "JP18") (pin "6") (pinfunction "6_6") (pintype "passive"))
    )
    (net (code "189") (name "unconnected-(JP18-Pad7)") (class "Default")
      (node (ref "JP18") (pin "7") (pinfunction "7_7") (pintype "passive"))
    )
    (net (code "190") (name "unconnected-(JP18-Pad8)") (class "Default")
      (node (ref "JP18") (pin "8") (pinfunction "8_8") (pintype "passive"))
    )
    (net (code "191") (name "unconnected-(JP18-Pad9)") (class "Default")
      (node (ref "JP18") (pin "9") (pinfunction "9_9") (pintype "passive"))
    )
    (net (code "192") (name "unconnected-(JP18-Pad10)") (class "Default")
      (node (ref "JP18") (pin "10") (pinfunction "10_10") (pintype "passive"))
    )
    (net (code "193") (name "unconnected-(JP18-Pad11)") (class "Default")
      (node (ref "JP18") (pin "11") (pinfunction "11_11") (pintype "passive"))
    )
    (net (code "194") (name "unconnected-(JP18-Pad12)") (class "Default")
      (node (ref "JP18") (pin "12") (pinfunction "12_12") (pintype "passive"))
    )
    (net (code "195") (name "unconnected-(U1-PadAREF)") (class "Default")
      (node (ref "U1") (pin "AREF") (pinfunction "AREF_AREF") (pintype "bidirectional"))
    )
    (net (code "196") (name "unconnected-(U1-PadIOREF)") (class "Default")
      (node (ref "U1") (pin "IOREF") (pinfunction "IOREF_IOREF") (pintype "output"))
    )
    (net (code "197") (name "unconnected-(U1-PadRESERVED)") (class "Default")
      (node (ref "U1") (pin "RESERVED") (pinfunction "RESERVED_RESERVED") (pintype "no_connect"))
    )
    (net (code "198") (name "unconnected-(U1-PadSCL)") (class "Default")
      (node (ref "U1") (pin "SCL") (pinfunction "SCL_SCL") (pintype "bidirectional"))
    )
    (net (code "199") (name "unconnected-(U1-PadSDA)") (class "Default")
      (node (ref "U1") (pin "SDA") (pinfunction "SDA_SDA") (pintype "bidirectional"))
    )
  )
)
